# Receiver.net
KiCad netlist of a schematic drawn in Altium Designer
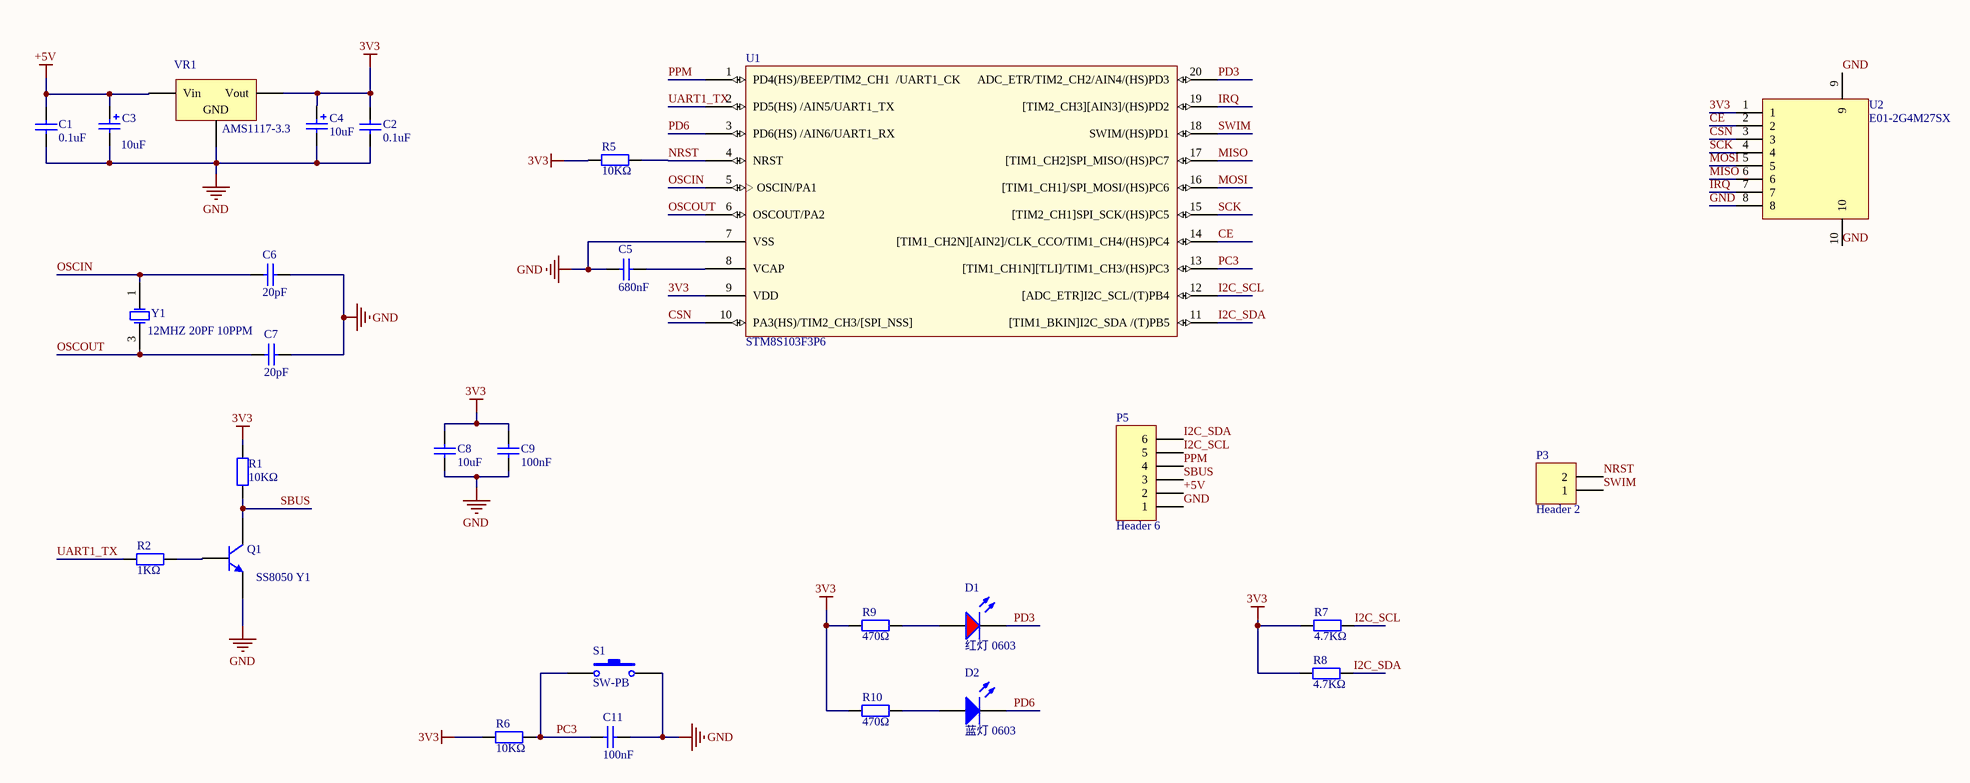
[diagram p0: Receiver.SchDoc]

(export (version "E")
  (design (tool "Eeschema 10.0.6"))
  (components
    (comp (ref "C1")
      (value "0.1uF")
      (footprint "0603_C")
      (description "贴片电容")
      (libsource (lib "Miscellaneous Devices LC") (part "0603 1uF (105) 10% 50V"))
    )
    (comp (ref "C2")
      (value "0.1uF")
      (footprint "0603_C")
      (description "贴片电容")
      (libsource (lib "Miscellaneous Devices LC") (part "0603 1uF (105) 10% 50V"))
    )
    (comp (ref "C3")
      (value "10uF")
      (footprint "CASE-A_3216")
      (description "钽电容")
      (libsource (lib "Miscellaneous Devices LC") (part "3216 10uF (106) 10% 16V"))
    )
    (comp (ref "C4")
      (value "10uF")
      (footprint "CASE-A_3216")
      (description "钽电容")
      (libsource (lib "Miscellaneous Devices LC") (part "3216 10uF (106) 10% 16V"))
    )
    (comp (ref "C5")
      (value "680nF")
      (footprint "0603_C")
      (description "贴片电容")
      (libsource (lib "Miscellaneous Devices LC") (part "0603 1uF (105) 10% 50V"))
    )
    (comp (ref "C6")
      (value "20pF")
      (footprint "0603_C")
      (description "贴片电容")
      (libsource (lib "Miscellaneous Devices LC") (part "0603 1.0pF (010) 0.25pF 50V"))
    )
    (comp (ref "C7")
      (value "20pF")
      (footprint "0603_C")
      (description "贴片电容")
      (libsource (lib "Miscellaneous Devices LC") (part "0603 1.0pF (010) 0.25pF 50V"))
    )
    (comp (ref "C8")
      (value "10uF")
      (footprint "0603_C")
      (description "贴片电容")
      (libsource (lib "Miscellaneous Devices LC") (part "0603 1uF (105) 10% 50V"))
    )
    (comp (ref "C9")
      (value "100nF")
      (footprint "0603_C")
      (description "贴片电容")
      (libsource (lib "Miscellaneous Devices LC") (part "0603 1uF (105) 10% 50V"))
    )
    (comp (ref "C11")
      (value "100nF")
      (footprint "0603_C")
      (description "贴片电容")
      (libsource (lib "Miscellaneous Devices LC") (part "0603 1uF (105) 10% 50V"))
    )
    (comp (ref "D1")
      (value "红灯 0603")
      (footprint "0603_LED_S1")
      (description "发光二极管")
      (libsource (lib "Miscellaneous Devices LC") (part "0603 红灯"))
    )
    (comp (ref "D2")
      (value "蓝灯 0603")
      (footprint "0603_LED_S1")
      (description "发光二极管")
      (libsource (lib "Miscellaneous Devices LC") (part "0603 蓝灯"))
    )
    (comp (ref "P3")
      (value "Header 2")
      (footprint "HDR1X2")
      (description "Header, 2-Pin")
      (fields (field (name "PUBLISHER") "Altium Limited"))
      (libsource (lib "Miscellaneous Connectors") (part "Header 2"))
    )
    (comp (ref "P5")
      (value "Header 6")
      (footprint "HDR1X6")
      (description "Header, 6-Pin")
      (fields (field (name "PUBLISHER") "Altium Limited"))
      (libsource (lib "Miscellaneous Connectors") (part "Header 6"))
    )
    (comp (ref "Q1")
      (value "SS8050 Y1")
      (footprint "SOT-23(SOT-23-3)")
      (description "三极管")
      (libsource (lib "Miscellaneous Devices LC") (part "SOT-23 SS8050 Y1"))
    )
    (comp (ref "R1")
      (value "10KΩ")
      (footprint "0603_R")
      (description "贴片电阻")
      (libsource (lib "") (part "0603 1KΩ (1001) 1%_1"))
    )
    (comp (ref "R2")
      (value "1KΩ")
      (footprint "0603_R")
      (description "贴片电阻")
      (libsource (lib "") (part "0603 1KΩ (1001) 1%_2"))
    )
    (comp (ref "R5")
      (value "10KΩ")
      (footprint "0603_R")
      (description "贴片电阻")
      (libsource (lib "Miscellaneous Devices LC") (part "0603 1KΩ (1001) 1%"))
    )
    (comp (ref "R6")
      (value "10KΩ")
      (footprint "0603_R")
      (description "贴片电阻")
      (libsource (lib "Miscellaneous Devices LC") (part "0603 1KΩ (1001) 1%"))
    )
    (comp (ref "R7")
      (value "4.7KΩ")
      (footprint "0603_R")
      (description "贴片电阻")
      (libsource (lib "Miscellaneous Devices LC") (part "0603 1.5KΩ (1501) 1%"))
    )
    (comp (ref "R8")
      (value "4.7KΩ")
      (footprint "0603_R")
      (description "贴片电阻")
      (libsource (lib "Miscellaneous Devices LC") (part "0603 1.5KΩ (1501) 1%"))
    )
    (comp (ref "R9")
      (value "470Ω")
      (footprint "0603_R")
      (description "贴片电阻")
      (libsource (lib "Miscellaneous Devices LC") (part "0603 1.1KΩ (1101) 1%"))
    )
    (comp (ref "R10")
      (value "470Ω")
      (footprint "0603_R")
      (description "贴片电阻")
      (libsource (lib "Miscellaneous Devices LC") (part "0603 1.1KΩ (1101) 1%"))
    )
    (comp (ref "S1")
      (value "SW-PB")
      (footprint "SMD_KEY_4P")
      (description "Switch")
      (fields (field (name "PUBLISHER") "Altium Limited"))
      (libsource (lib "Miscellaneous Devices") (part "SW-PB"))
    )
    (comp (ref "U1")
      (value "STM8S103F3P6")
      (footprint "TSSOP-20")
      (description "MCU")
      (libsource (lib "Miscellaneous Devices LC") (part "STM8S103F3P6"))
    )
    (comp (ref "U2")
      (value "E01-2G4M27SX")
      (footprint "E01-2G4M27SX")
      (libsource (lib "Receiver_Schlib") (part "E01-2G4M27SX"))
    )
    (comp (ref "VR1")
      (value "AMS1117-3.3")
      (footprint "SOT-223")
      (description "低压差线性稳压(LDO)")
      (libsource (lib "Miscellaneous Devices LC") (part "SOT-223 AMS1117-3.3"))
    )
    (comp (ref "Y1")
      (value "12MHZ 20PF 10PPM")
      (footprint "SMD-3225_4P")
      (description "贴片晶振")
      (libsource (lib "Miscellaneous Devices LC") (part "SMD-3225_4P  12MHZ 20PF 10PPM"))
    )
  )
  (nets
    (net (code "1") (name "+5V") (class "Default")
      (node (ref "C1") (pin "2") (pinfunction "2_2") (pintype "passive"))
      (node (ref "C3") (pin "1") (pinfunction "1_1") (pintype "passive"))
      (node (ref "P5") (pin "2") (pinfunction "2_2") (pintype "passive"))
      (node (ref "VR1") (pin "3") (pinfunction "Vin_3") (pintype "passive"))
    )
    (net (code "2") (name "/CE") (class "Default")
      (node (ref "U1") (pin "14") (pinfunction "[TIM1_CH2N][AIN2]/CLK_CCO/TIM1_CH4/(HS)PC4_14") (pintype "bidirectional"))
      (node (ref "U2") (pin "2") (pinfunction "2_2") (pintype "passive"))
    )
    (net (code "3") (name "/CSN") (class "Default")
      (node (ref "U1") (pin "10") (pinfunction "PA3(HS)/TIM2_CH3/[SPI_NSS]_10") (pintype "bidirectional"))
      (node (ref "U2") (pin "3") (pinfunction "3_3") (pintype "passive"))
    )
    (net (code "4") (name "/I2C_SCL") (class "Default")
      (node (ref "P5") (pin "5") (pinfunction "5_5") (pintype "passive"))
      (node (ref "R7") (pin "2") (pinfunction "2_2") (pintype "passive"))
      (node (ref "U1") (pin "12") (pinfunction "[ADC_ETR]I2C_SCL/(T)PB4_12") (pintype "bidirectional"))
    )
    (net (code "5") (name "/I2C_SDA") (class "Default")
      (node (ref "P5") (pin "6") (pinfunction "6_6") (pintype "passive"))
      (node (ref "R8") (pin "2") (pinfunction "2_2") (pintype "passive"))
      (node (ref "U1") (pin "11") (pinfunction "[TIM1_BKIN]I2C_SDA_/(T)PB5_11") (pintype "bidirectional"))
    )
    (net (code "6") (name "/IRQ") (class "Default")
      (node (ref "U1") (pin "19") (pinfunction "[TIM2_CH3][AIN3]/(HS)PD2_19") (pintype "bidirectional"))
      (node (ref "U2") (pin "7") (pinfunction "7_7") (pintype "passive"))
    )
    (net (code "7") (name "/MISO") (class "Default")
      (node (ref "U1") (pin "17") (pinfunction "[TIM1_CH2]SPI_MISO/(HS)PC7_17") (pintype "bidirectional"))
      (node (ref "U2") (pin "6") (pinfunction "6_6") (pintype "passive"))
    )
    (net (code "8") (name "/MOSI") (class "Default")
      (node (ref "U1") (pin "16") (pinfunction "[TIM1_CH1]/SPI_MOSI/(HS)PC6_16") (pintype "bidirectional"))
      (node (ref "U2") (pin "5") (pinfunction "5_5") (pintype "passive"))
    )
    (net (code "9") (name "/NRST") (class "Default")
      (node (ref "P3") (pin "2") (pinfunction "2_2") (pintype "passive"))
      (node (ref "R5") (pin "1") (pinfunction "1_1") (pintype "passive"))
      (node (ref "U1") (pin "4") (pinfunction "NRST_4") (pintype "bidirectional"))
    )
    (net (code "10") (name "/OSCIN") (class "Default")
      (node (ref "C6") (pin "1") (pinfunction "1_1") (pintype "passive"))
      (node (ref "U1") (pin "5") (pinfunction "OSCIN/PA1_5") (pintype "bidirectional"))
      (node (ref "Y1") (pin "1") (pinfunction "OSC1_1") (pintype "passive"))
    )
    (net (code "11") (name "/OSCOUT") (class "Default")
      (node (ref "C7") (pin "2") (pinfunction "2_2") (pintype "passive"))
      (node (ref "U1") (pin "6") (pinfunction "OSCOUT/PA2_6") (pintype "bidirectional"))
      (node (ref "Y1") (pin "3") (pinfunction "OSC2_3") (pintype "passive"))
    )
    (net (code "12") (name "/PC3") (class "Default")
      (node (ref "C11") (pin "2") (pinfunction "2_2") (pintype "passive"))
      (node (ref "R6") (pin "1") (pinfunction "1_1") (pintype "passive"))
      (node (ref "S1") (pin "1") (pinfunction "1_1") (pintype "passive"))
      (node (ref "U1") (pin "13") (pinfunction "[TIM1_CH1N][TLI]/TIM1_CH3/(HS)PC3_13") (pintype "bidirectional"))
    )
    (net (code "13") (name "/PD3") (class "Default")
      (node (ref "D1") (pin "K") (pinfunction "K_K") (pintype "passive"))
      (node (ref "U1") (pin "20") (pinfunction "ADC_ETR/TIM2_CH2/AIN4/(HS)PD3_20") (pintype "bidirectional"))
    )
    (net (code "14") (name "/PD6") (class "Default")
      (node (ref "D2") (pin "K") (pinfunction "K_K") (pintype "passive"))
      (node (ref "U1") (pin "3") (pinfunction "PD6(HS)_/AIN6/UART1_RX_3") (pintype "bidirectional"))
    )
    (net (code "15") (name "/PPM") (class "Default")
      (node (ref "P5") (pin "4") (pinfunction "4_4") (pintype "passive"))
      (node (ref "U1") (pin "1") (pinfunction "PD4(HS)/BEEP/TIM2_CH1__/UART1_CK_1") (pintype "bidirectional"))
    )
    (net (code "16") (name "/SBUS") (class "Default")
      (node (ref "P5") (pin "3") (pinfunction "3_3") (pintype "passive"))
      (node (ref "Q1") (pin "3") (pinfunction "C_3") (pintype "passive"))
      (node (ref "R1") (pin "1") (pinfunction "1_1") (pintype "passive"))
    )
    (net (code "17") (name "/SCK") (class "Default")
      (node (ref "U1") (pin "15") (pinfunction "[TIM2_CH1]SPI_SCK/(HS)PC5_15") (pintype "bidirectional"))
      (node (ref "U2") (pin "4") (pinfunction "4_4") (pintype "passive"))
    )
    (net (code "18") (name "/SWIM") (class "Default")
      (node (ref "P3") (pin "1") (pinfunction "1_1") (pintype "passive"))
      (node (ref "U1") (pin "18") (pinfunction "SWIM/(HS)PD1_18") (pintype "bidirectional"))
    )
    (net (code "19") (name "/UART1_TX") (class "Default")
      (node (ref "R2") (pin "1") (pinfunction "1_1") (pintype "passive"))
      (node (ref "U1") (pin "2") (pinfunction "PD5(HS)_/AIN5/UART1_TX_2") (pintype "bidirectional"))
    )
    (net (code "20") (name "3V3") (class "Default")
      (node (ref "C2") (pin "2") (pinfunction "2_2") (pintype "passive"))
      (node (ref "C4") (pin "1") (pinfunction "1_1") (pintype "passive"))
      (node (ref "C8") (pin "2") (pinfunction "2_2") (pintype "passive"))
      (node (ref "C9") (pin "2") (pinfunction "2_2") (pintype "passive"))
      (node (ref "R1") (pin "2") (pinfunction "2_2") (pintype "passive"))
      (node (ref "R10") (pin "1") (pinfunction "1_1") (pintype "passive"))
      (node (ref "R5") (pin "2") (pinfunction "2_2") (pintype "passive"))
      (node (ref "R6") (pin "2") (pinfunction "2_2") (pintype "passive"))
      (node (ref "R7") (pin "1") (pinfunction "1_1") (pintype "passive"))
      (node (ref "R8") (pin "1") (pinfunction "1_1") (pintype "passive"))
      (node (ref "R9") (pin "1") (pinfunction "1_1") (pintype "passive"))
      (node (ref "U1") (pin "9") (pinfunction "VDD_9") (pintype "power_in"))
      (node (ref "U2") (pin "1") (pinfunction "1_1") (pintype "passive"))
      (node (ref "VR1") (pin "2") (pinfunction "Vout_2") (pintype "passive"))
    )
    (net (code "21") (name "GND") (class "Default")
      (node (ref "C1") (pin "1") (pinfunction "1_1") (pintype "passive"))
      (node (ref "C11") (pin "1") (pinfunction "1_1") (pintype "passive"))
      (node (ref "C2") (pin "1") (pinfunction "1_1") (pintype "passive"))
      (node (ref "C3") (pin "2") (pinfunction "2_2") (pintype "passive"))
      (node (ref "C4") (pin "2") (pinfunction "2_2") (pintype "passive"))
      (node (ref "C5") (pin "2") (pinfunction "2_2") (pintype "passive"))
      (node (ref "C6") (pin "2") (pinfunction "2_2") (pintype "passive"))
      (node (ref "C7") (pin "1") (pinfunction "1_1") (pintype "passive"))
      (node (ref "C8") (pin "1") (pinfunction "1_1") (pintype "passive"))
      (node (ref "C9") (pin "1") (pinfunction "1_1") (pintype "passive"))
      (node (ref "P5") (pin "1") (pinfunction "1_1") (pintype "passive"))
      (node (ref "Q1") (pin "2") (pinfunction "E_2") (pintype "passive"))
      (node (ref "S1") (pin "2") (pinfunction "2_2") (pintype "passive"))
      (node (ref "U1") (pin "7") (pinfunction "VSS_7") (pintype "power_in"))
      (node (ref "U2") (pin "10") (pinfunction "10_10") (pintype "passive"))
      (node (ref "U2") (pin "8") (pinfunction "8_8") (pintype "passive"))
      (node (ref "U2") (pin "9") (pinfunction "9_9") (pintype "passive"))
      (node (ref "VR1") (pin "1") (pinfunction "GND_1") (pintype "passive"))
    )
    (net (code "22") (name "Net-(D1-PadA)") (class "Default")
      (node (ref "D1") (pin "A") (pinfunction "A_A") (pintype "passive"))
      (node (ref "R9") (pin "2") (pinfunction "2_2") (pintype "passive"))
    )
    (net (code "23") (name "Net-(D2-PadA)") (class "Default")
      (node (ref "D2") (pin "A") (pinfunction "A_A") (pintype "passive"))
      (node (ref "R10") (pin "2") (pinfunction "2_2") (pintype "passive"))
    )
    (net (code "24") (name "Net-(Q1-B)") (class "Default")
      (node (ref "Q1") (pin "1") (pinfunction "B_1") (pintype "passive"))
      (node (ref "R2") (pin "2") (pinfunction "2_2") (pintype "passive"))
    )
    (net (code "25") (name "Net-(U1-VCAP)") (class "Default")
      (node (ref "C5") (pin "1") (pinfunction "1_1") (pintype "passive"))
      (node (ref "U1") (pin "8") (pinfunction "VCAP_8") (pintype "power_in"))
    )
  )
)
